# SCH_Hacker-Card_2025-04-16.net
KiCad netlist of a schematic drawn in EasyEDA
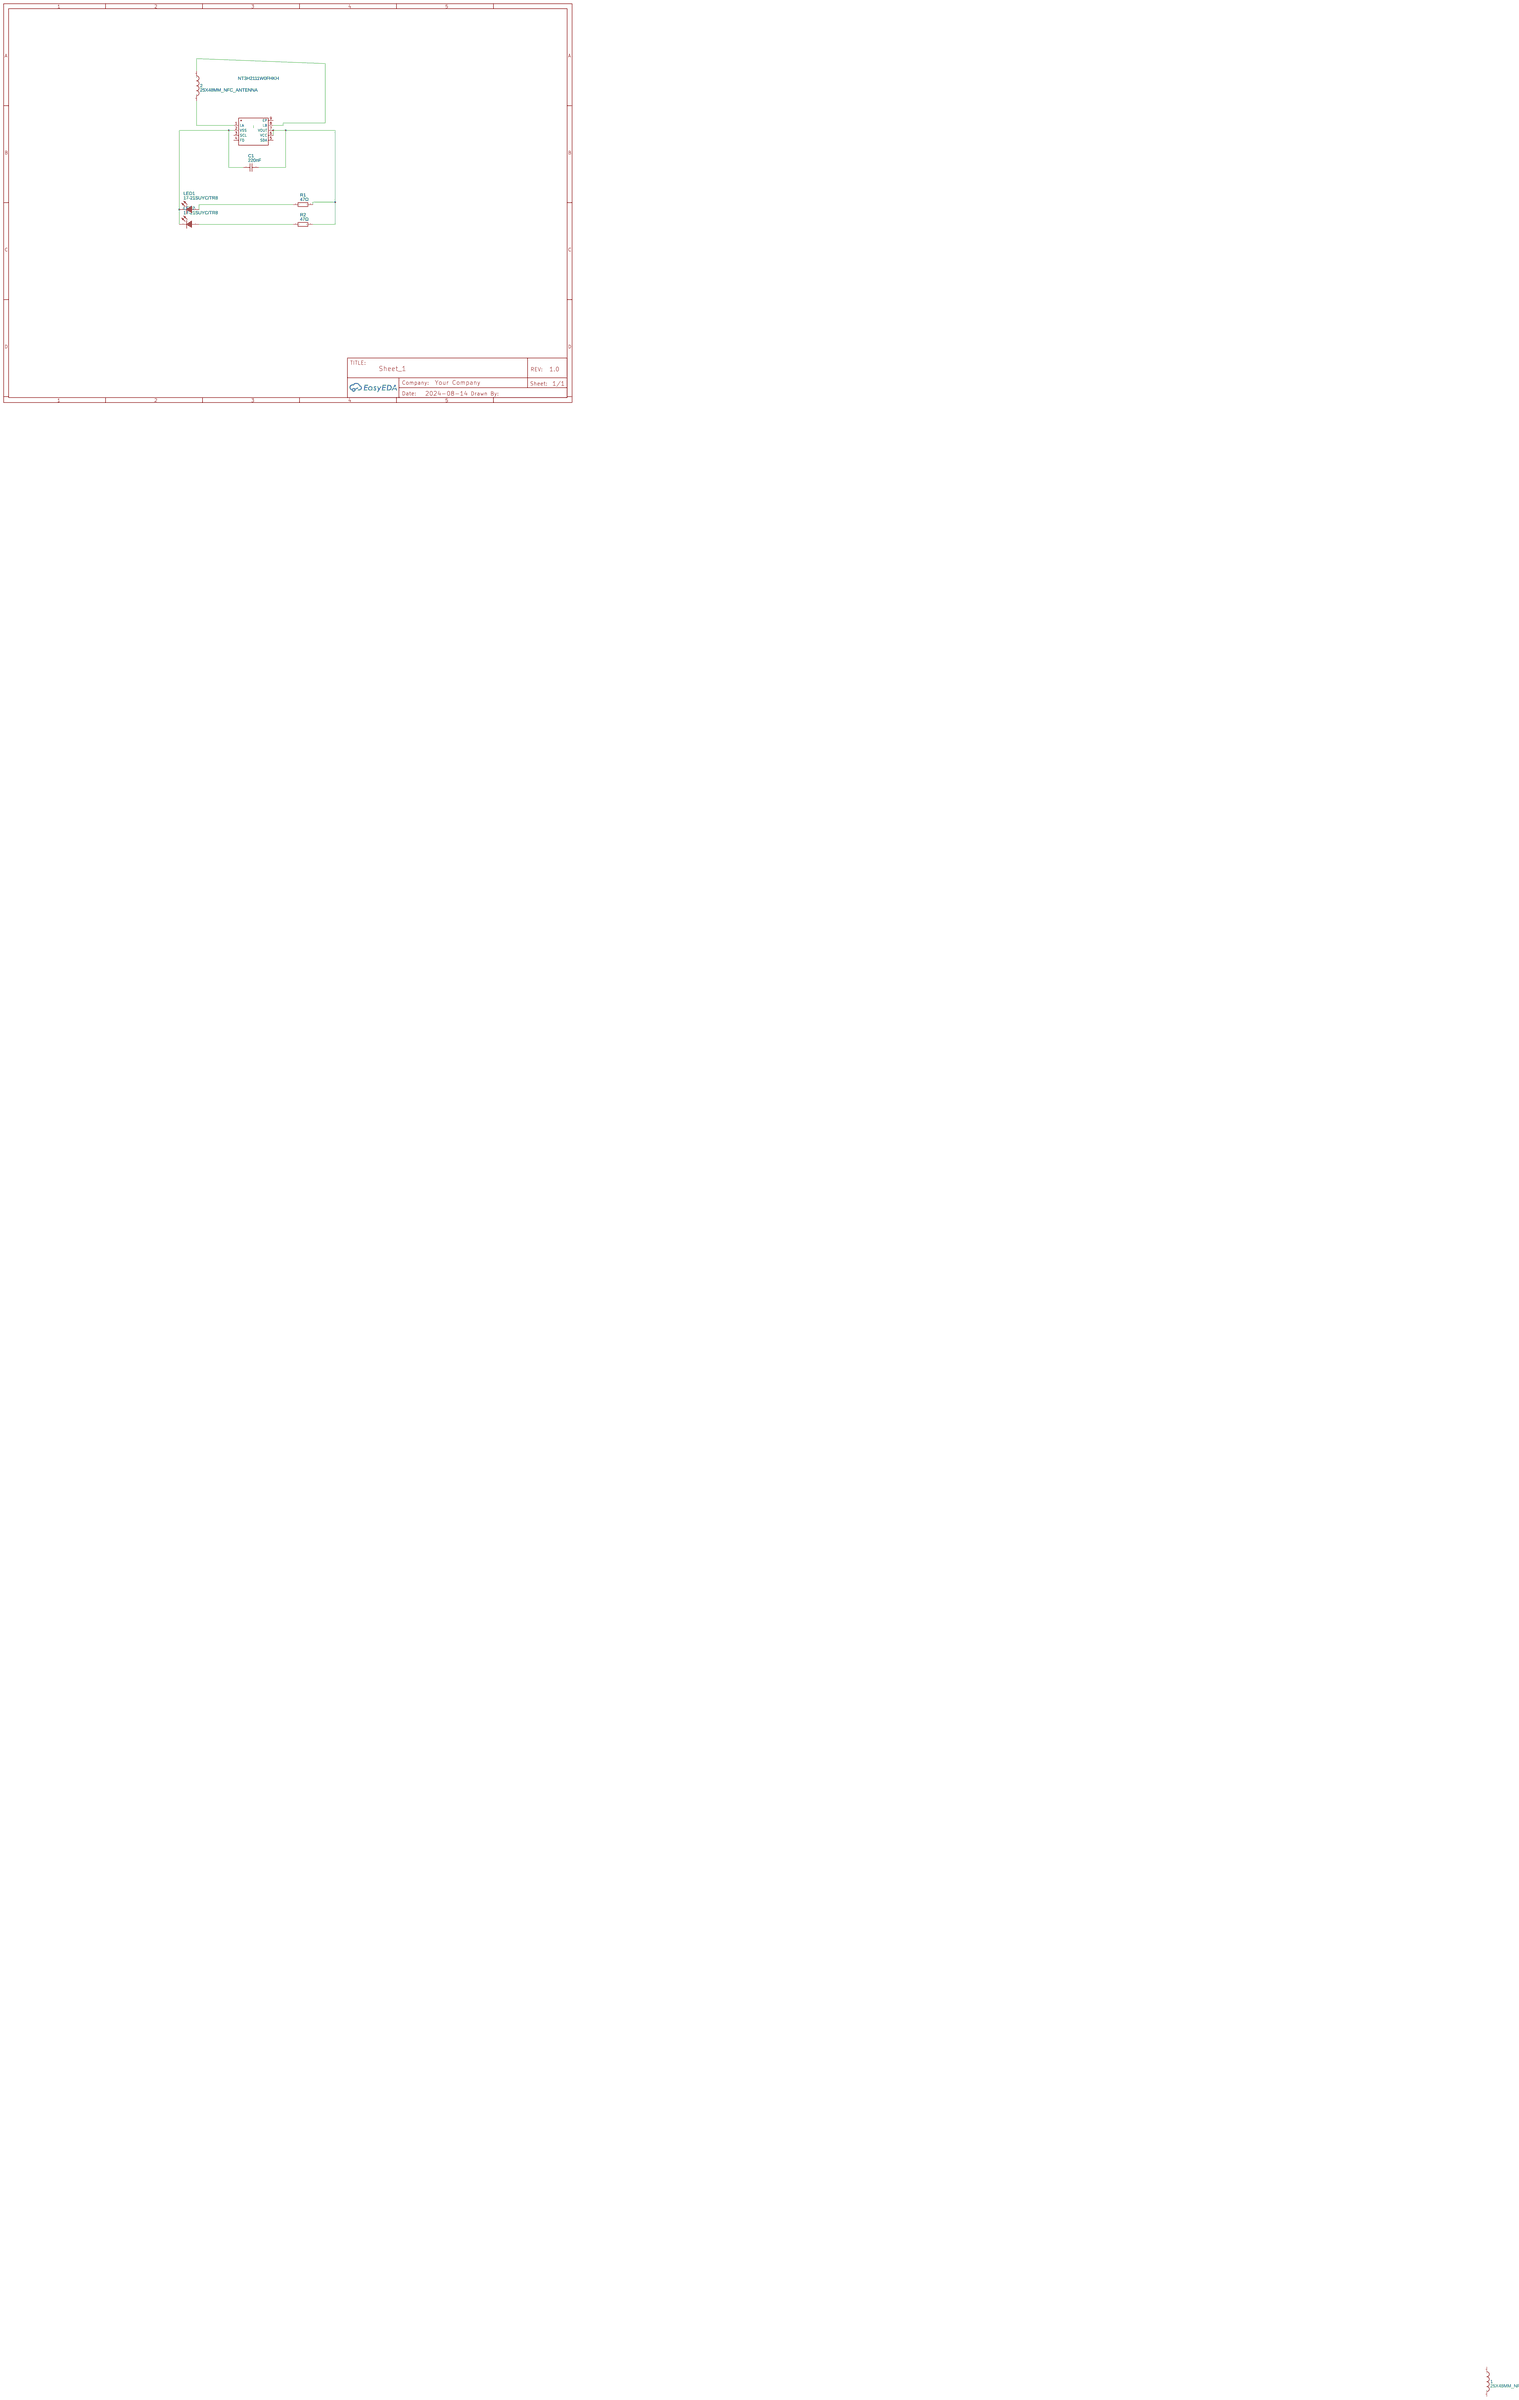
[diagram p0: schematic sheet]

(export (version "E")
  (design (tool "Eeschema 10.0.6"))
  (components
    (comp (ref "1") (value "25X48MM_NFC_ANTENNA") (libsource (lib "") (part "25X48MM_NFC_ANTENNA")))
    (comp (ref "2") (value "25X48MM_NFC_ANTENNA") (libsource (lib "") (part "25X48MM_NFC_ANTENNA")))
    (comp (ref "C1")
      (value "220nF")
      (fields
        (field (name "Manufacturer Part") "CL10B224KA8NNNC")
        (field (name "Manufacturer") "SAMSUNG(三星)")
      )
      (libsource (lib "") (part "CL10B224KA8NNNC"))
    )
    (comp (ref "LED1")
      (value "17-21SUYC/TR8")
      (fields (field (name "Manufacturer Part") "KT-0805黄灯") (field (name "Manufacturer") "KENTO"))
      (libsource (lib "") (part "17-21SUYC/TR8"))
    )
    (comp (ref "LED2")
      (value "17-21SUYC/TR8")
      (fields (field (name "Manufacturer Part") "KT-0805黄灯") (field (name "Manufacturer") "KENTO"))
      (libsource (lib "") (part "17-21SUYC/TR8"))
    )
    (comp (ref "R1")
      (value "47Ω")
      (fields
        (field (name "Manufacturer Part") "0603WAF470JT5E")
        (field (name "Manufacturer") "UNI-ROYAL(厚声)")
      )
      (libsource (lib "") (part "0603WAF470JT5E"))
    )
    (comp (ref "R2")
      (value "47Ω")
      (fields
        (field (name "Manufacturer Part") "0603WAF470JT5E")
        (field (name "Manufacturer") "UNI-ROYAL(厚声)")
      )
      (libsource (lib "") (part "0603WAF470JT5E"))
    )
    (comp (ref "U1")
      (value "NT3H2111W0FHKH")
      (fields (field (name "Manufacturer") "NXP(恩智浦)"))
      (libsource (lib "") (part "NT3H2111W0FHKH"))
    )
  )
  (nets
    (net (code "1") (name "Net-(LED1-+)") (class "Default")
      (node (ref "LED1") (pin "1") (pinfunction "+_1") (pintype "unspecified"))
      (node (ref "R1") (pin "1") (pinfunction "1_1") (pintype "input"))
    )
    (net (code "2") (name "Net-(LED1--)") (class "Default")
      (node (ref "C1") (pin "1") (pinfunction "1_1") (pintype "input"))
      (node (ref "LED1") (pin "2") (pinfunction "-_2") (pintype "unspecified"))
      (node (ref "LED2") (pin "2") (pinfunction "-_2") (pintype "unspecified"))
      (node (ref "U1") (pin "2") (pinfunction "VSS_2") (pintype "unspecified"))
    )
    (net (code "3") (name "Net-(LED2-+)") (class "Default")
      (node (ref "LED2") (pin "1") (pinfunction "+_1") (pintype "unspecified"))
      (node (ref "R2") (pin "1") (pinfunction "1_1") (pintype "input"))
    )
    (net (code "4") (name "Net-(U1-LA)") (class "Default")
      (node (ref "2") (pin "P$2") (pinfunction "P$2_P$2") (pintype "bidirectional"))
      (node (ref "U1") (pin "1") (pinfunction "LA_1") (pintype "unspecified"))
    )
    (net (code "5") (name "Net-(U1-LB)") (class "Default")
      (node (ref "2") (pin "P$1") (pinfunction "P$1_P$1") (pintype "bidirectional"))
      (node (ref "U1") (pin "8") (pinfunction "LB_8") (pintype "unspecified"))
    )
    (net (code "6") (name "Net-(U1-VCC)") (class "Default")
      (node (ref "C1") (pin "2") (pinfunction "2_2") (pintype "input"))
      (node (ref "R1") (pin "2") (pinfunction "2_2") (pintype "input"))
      (node (ref "R2") (pin "2") (pinfunction "2_2") (pintype "input"))
      (node (ref "U1") (pin "6") (pinfunction "VCC_6") (pintype "unspecified"))
      (node (ref "U1") (pin "7") (pinfunction "VOUT_7") (pintype "unspecified"))
    )
    (net (code "7") (name "unconnected-(1-PadP$1)") (class "Default")
      (node (ref "1") (pin "P$1") (pinfunction "P$1_P$1") (pintype "bidirectional"))
    )
    (net (code "8") (name "unconnected-(1-PadP$2)") (class "Default")
      (node (ref "1") (pin "P$2") (pinfunction "P$2_P$2") (pintype "bidirectional"))
    )
    (net (code "9") (name "unconnected-(U1-EP-Pad9)") (class "Default")
      (node (ref "U1") (pin "9") (pinfunction "EP_9") (pintype "unspecified"))
    )
    (net (code "10") (name "unconnected-(U1-FD-Pad4)") (class "Default")
      (node (ref "U1") (pin "4") (pinfunction "FD_4") (pintype "unspecified"))
    )
    (net (code "11") (name "unconnected-(U1-SCL-Pad3)") (class "Default")
      (node (ref "U1") (pin "3") (pinfunction "SCL_3") (pintype "unspecified"))
    )
    (net (code "12") (name "unconnected-(U1-SDA-Pad5)") (class "Default")
      (node (ref "U1") (pin "5") (pinfunction "SDA_5") (pintype "unspecified"))
    )
  )
)
